# module_rev1.net
KiCad netlist of a schematic drawn in Altium Designer
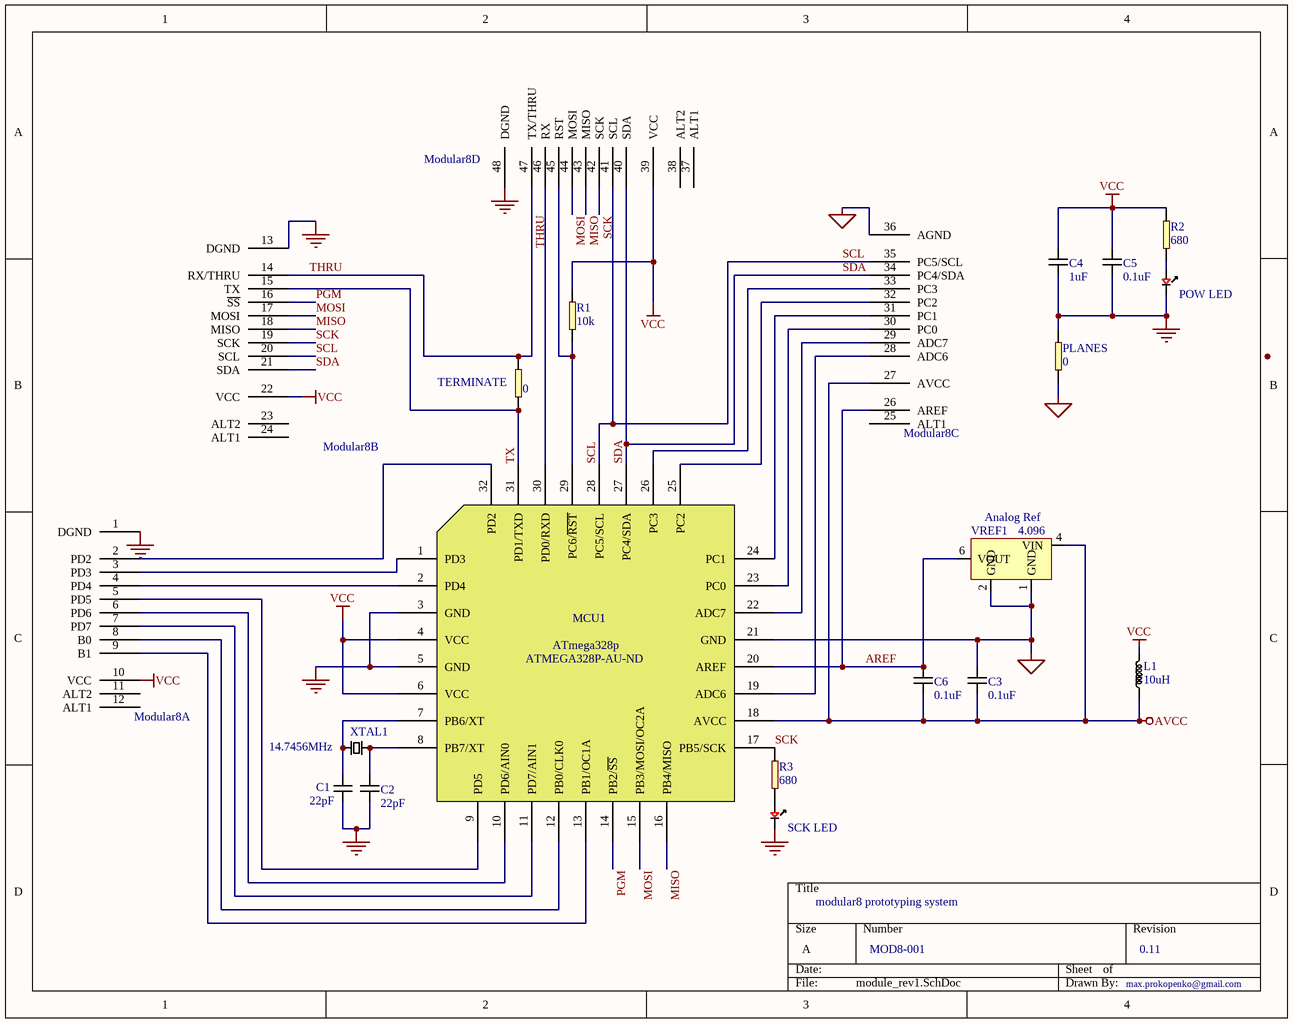
[diagram p0: module_rev1.SchDoc]

(export (version "E")
  (design (tool "Eeschema 10.0.6"))
  (components
    (comp (ref "C1")
      (value "C 22pF 50V")
      (footprint "0603")
      (fields (field (name "C") "22pF"))
      (libsource (lib "") (part "C 22pF 50V_1"))
    )
    (comp (ref "C2")
      (value "C 22pF 50V")
      (footprint "0603")
      (fields (field (name "C") "22pF"))
      (libsource (lib "RLC") (part "C 22pF 50V"))
    )
    (comp (ref "C3")
      (value "C 0.1uF 25V")
      (footprint "0603")
      (fields (field (name "C") "0.1uF"))
      (libsource (lib "RLC") (part "C 0.1uF 25V"))
    )
    (comp (ref "C4")
      (value "C 1uF 25V")
      (footprint "0603")
      (fields (field (name "C") "1uF"))
      (libsource (lib "RLC") (part "C 1uF 25V"))
    )
    (comp (ref "C5")
      (value "C 0.1uF 25V")
      (footprint "0603")
      (fields (field (name "C") "0.1uF"))
      (libsource (lib "RLC") (part "C 0.1uF 25V"))
    )
    (comp (ref "C6")
      (value "C 0.1uF 25V")
      (footprint "0603")
      (fields (field (name "C") "0.1uF"))
      (libsource (lib "RLC") (part "C 0.1uF 25V"))
    )
    (comp (ref "L1")
      (value "L 10uH")
      (footprint "0603")
      (fields (field (name "L") "10uH"))
      (libsource (lib "RLC") (part "L 10uH"))
    )
    (comp (ref "MCU1")
      (value "ATmega328p")
      (footprint "ATmega328p TQFP")
      (fields (field (name "SUPPLIER PART NUMBER 1") "ATMEGA328P-AU-ND"))
      (libsource (lib "OpBots") (part "ATmega328p"))
    )
    (comp (ref "Modular8")
      (value "Modular8")
      (footprint "modular8")
      (libsource (lib "OpBots") (part "Modular8"))
    )
    (comp (ref "PLANES")
      (value "R 0")
      (footprint "0603")
      (fields (field (name "R") "0"))
      (libsource (lib "") (part "R 0_1"))
    )
    (comp (ref "POW LED") (value "LEDR") (footprint "0603") (libsource (lib "OpBots") (part "LEDR")))
    (comp (ref "R1")
      (value "R 10k")
      (footprint "0603")
      (fields (field (name "R") "10k"))
      (libsource (lib "RLC") (part "R 10k"))
    )
    (comp (ref "R2")
      (value "R 680")
      (footprint "0603")
      (fields (field (name "R") "680"))
      (libsource (lib "RLC") (part "R 680"))
    )
    (comp (ref "R3")
      (value "R 680")
      (footprint "0603")
      (fields (field (name "R") "680"))
      (libsource (lib "RLC") (part "R 680"))
    )
    (comp (ref "SCK LED") (value "LEDR") (footprint "0603") (libsource (lib "OpBots") (part "LEDR")))
    (comp (ref "TERMINATE")
      (value "R 0")
      (footprint "0603")
      (fields (field (name "R") "0"))
      (libsource (lib "RLC") (part "R 0"))
    )
    (comp (ref "VREF1")
      (value "Analog Ref")
      (footprint "TSOT-23-6")
      (fields (field (name "VREF") "4.096"))
      (libsource (lib "OpBots") (part "LT1790BCS6"))
    )
    (comp (ref "XTAL1")
      (value "XTAL 14.7456MHz")
      (footprint "XTAL CSM-3X")
      (fields (field (name "FREQUENCY") "14.7456MHz"))
      (libsource (lib "OpBots") (part "XTAL 14.7456MHz"))
    )
  )
  (nets
    (net (code "1") (name "/AREF") (class "Default")
      (node (ref "C6") (pin "1") (pintype "passive"))
      (node (ref "MCU1") (pin "20") (pinfunction "AREF_20") (pintype "passive"))
      (node (ref "Modular8") (pin "26") (pinfunction "AREF_26") (pintype "passive"))
      (node (ref "VREF1") (pin "6") (pinfunction "VOUT_6") (pintype "passive"))
    )
    (net (code "2") (name "/MISO") (class "Default")
      (node (ref "MCU1") (pin "16") (pinfunction "PB4/MISO_16") (pintype "passive"))
      (node (ref "Modular8") (pin "18") (pinfunction "MISO_18") (pintype "passive"))
      (node (ref "Modular8") (pin "43") (pinfunction "MISO_43") (pintype "passive"))
    )
    (net (code "3") (name "/MOSI") (class "Default")
      (node (ref "MCU1") (pin "15") (pinfunction "PB3/MOSI/OC2A_15") (pintype "passive"))
      (node (ref "Modular8") (pin "17") (pinfunction "MOSI_17") (pintype "passive"))
      (node (ref "Modular8") (pin "44") (pinfunction "MOSI_44") (pintype "passive"))
    )
    (net (code "4") (name "/PGM") (class "Default")
      (node (ref "MCU1") (pin "14") (pinfunction "PB2/~{SS}_14") (pintype "passive"))
      (node (ref "Modular8") (pin "16") (pinfunction "~{SS}_16") (pintype "passive"))
    )
    (net (code "5") (name "/SCK") (class "Default")
      (node (ref "MCU1") (pin "17") (pinfunction "PB5/SCK_17") (pintype "passive"))
      (node (ref "Modular8") (pin "19") (pinfunction "SCK_19") (pintype "passive"))
      (node (ref "Modular8") (pin "42") (pinfunction "SCK_42") (pintype "passive"))
      (node (ref "R3") (pin "1") (pintype "passive"))
    )
    (net (code "6") (name "/SCL") (class "Default")
      (node (ref "MCU1") (pin "28") (pinfunction "PC5/SCL_28") (pintype "passive"))
      (node (ref "Modular8") (pin "20") (pinfunction "SCL_20") (pintype "passive"))
      (node (ref "Modular8") (pin "35") (pinfunction "PC5/SCL_35") (pintype "passive"))
      (node (ref "Modular8") (pin "41") (pinfunction "SCL_41") (pintype "passive"))
    )
    (net (code "7") (name "/SDA") (class "Default")
      (node (ref "MCU1") (pin "27") (pinfunction "PC4/SDA_27") (pintype "passive"))
      (node (ref "Modular8") (pin "21") (pinfunction "SDA_21") (pintype "passive"))
      (node (ref "Modular8") (pin "34") (pinfunction "PC4/SDA_34") (pintype "passive"))
      (node (ref "Modular8") (pin "40") (pinfunction "SDA_40") (pintype "passive"))
    )
    (net (code "8") (name "/THRU") (class "Default")
      (node (ref "Modular8") (pin "14") (pinfunction "RX/THRU_14") (pintype "passive"))
      (node (ref "Modular8") (pin "47") (pinfunction "TX/THRU_47") (pintype "passive"))
      (node (ref "TERMINATE") (pin "1") (pintype "passive"))
    )
    (net (code "9") (name "/TX") (class "Default")
      (node (ref "MCU1") (pin "31") (pinfunction "PD1/TXD_31") (pintype "passive"))
      (node (ref "Modular8") (pin "15") (pinfunction "TX_15") (pintype "passive"))
      (node (ref "TERMINATE") (pin "2") (pintype "passive"))
    )
    (net (code "10") (name "AGND") (class "Default")
      (node (ref "C3") (pin "1") (pintype "passive"))
      (node (ref "MCU1") (pin "21") (pinfunction "GND_21") (pintype "passive"))
      (node (ref "Modular8") (pin "36") (pinfunction "AGND_36") (pintype "passive"))
      (node (ref "PLANES") (pin "1") (pintype "passive"))
      (node (ref "VREF1") (pin "1") (pinfunction "GND_1") (pintype "passive"))
      (node (ref "VREF1") (pin "2") (pinfunction "GND_2") (pintype "passive"))
    )
    (net (code "11") (name "AVCC") (class "Default")
      (node (ref "C3") (pin "2") (pintype "passive"))
      (node (ref "C6") (pin "2") (pintype "passive"))
      (node (ref "L1") (pin "2") (pintype "passive"))
      (node (ref "MCU1") (pin "18") (pinfunction "AVCC_18") (pintype "passive"))
      (node (ref "Modular8") (pin "27") (pinfunction "AVCC_27") (pintype "passive"))
      (node (ref "VREF1") (pin "4") (pinfunction "VIN_4") (pintype "passive"))
    )
    (net (code "12") (name "DGND") (class "Default")
      (node (ref "C1") (pin "1") (pintype "passive"))
      (node (ref "C2") (pin "2") (pintype "passive"))
      (node (ref "C4") (pin "2") (pintype "passive"))
      (node (ref "C5") (pin "2") (pintype "passive"))
      (node (ref "MCU1") (pin "3") (pinfunction "GND_3") (pintype "passive"))
      (node (ref "MCU1") (pin "5") (pinfunction "GND_5") (pintype "passive"))
      (node (ref "Modular8") (pin "1") (pinfunction "DGND_1") (pintype "passive"))
      (node (ref "Modular8") (pin "13") (pinfunction "DGND_13") (pintype "passive"))
      (node (ref "Modular8") (pin "48") (pinfunction "DGND_48") (pintype "passive"))
      (node (ref "PLANES") (pin "2") (pintype "passive"))
      (node (ref "POW LED") (pin "1") (pinfunction "K_1") (pintype "passive"))
      (node (ref "SCK LED") (pin "1") (pinfunction "K_1") (pintype "passive"))
    )
    (net (code "13") (name "Net-(MCU1-ADC6)") (class "Default")
      (node (ref "MCU1") (pin "19") (pinfunction "ADC6_19") (pintype "passive"))
      (node (ref "Modular8") (pin "28") (pinfunction "ADC6_28") (pintype "passive"))
    )
    (net (code "14") (name "Net-(MCU1-ADC7)") (class "Default")
      (node (ref "MCU1") (pin "22") (pinfunction "ADC7_22") (pintype "passive"))
      (node (ref "Modular8") (pin "29") (pinfunction "ADC7_29") (pintype "passive"))
    )
    (net (code "15") (name "Net-(MCU1-PB0{slash}CLK0)") (class "Default")
      (node (ref "MCU1") (pin "12") (pinfunction "PB0/CLK0_12") (pintype "passive"))
      (node (ref "Modular8") (pin "8") (pinfunction "B0_8") (pintype "passive"))
    )
    (net (code "16") (name "Net-(MCU1-PB1{slash}OC1A)") (class "Default")
      (node (ref "MCU1") (pin "13") (pinfunction "PB1/OC1A_13") (pintype "passive"))
      (node (ref "Modular8") (pin "9") (pinfunction "B1_9") (pintype "passive"))
    )
    (net (code "17") (name "Net-(MCU1-PB6{slash}XT)") (class "Default")
      (node (ref "C1") (pin "2") (pintype "passive"))
      (node (ref "MCU1") (pin "7") (pinfunction "PB6/XT_7") (pintype "passive"))
      (node (ref "XTAL1") (pin "1") (pintype "passive"))
    )
    (net (code "18") (name "Net-(MCU1-PB7{slash}XT)") (class "Default")
      (node (ref "C2") (pin "1") (pintype "passive"))
      (node (ref "MCU1") (pin "8") (pinfunction "PB7/XT_8") (pintype "passive"))
      (node (ref "XTAL1") (pin "2") (pintype "passive"))
    )
    (net (code "19") (name "Net-(MCU1-PC0)") (class "Default")
      (node (ref "MCU1") (pin "23") (pinfunction "PC0_23") (pintype "passive"))
      (node (ref "Modular8") (pin "30") (pinfunction "PC0_30") (pintype "passive"))
    )
    (net (code "20") (name "Net-(MCU1-PC1)") (class "Default")
      (node (ref "MCU1") (pin "24") (pinfunction "PC1_24") (pintype "passive"))
      (node (ref "Modular8") (pin "31") (pinfunction "PC1_31") (pintype "passive"))
    )
    (net (code "21") (name "Net-(MCU1-PC2)") (class "Default")
      (node (ref "MCU1") (pin "25") (pinfunction "PC2_25") (pintype "passive"))
      (node (ref "Modular8") (pin "32") (pinfunction "PC2_32") (pintype "passive"))
    )
    (net (code "22") (name "Net-(MCU1-PC3)") (class "Default")
      (node (ref "MCU1") (pin "26") (pinfunction "PC3_26") (pintype "passive"))
      (node (ref "Modular8") (pin "33") (pinfunction "PC3_33") (pintype "passive"))
    )
    (net (code "23") (name "Net-(MCU1-PC6{slash}~{RST})") (class "Default")
      (node (ref "MCU1") (pin "29") (pinfunction "PC6/~{RST}_29") (pintype "passive"))
      (node (ref "Modular8") (pin "45") (pinfunction "RST_45") (pintype "passive"))
      (node (ref "R1") (pin "2") (pintype "passive"))
    )
    (net (code "24") (name "Net-(MCU1-PD0{slash}RXD)") (class "Default")
      (node (ref "MCU1") (pin "30") (pinfunction "PD0/RXD_30") (pintype "passive"))
      (node (ref "Modular8") (pin "46") (pinfunction "RX_46") (pintype "passive"))
    )
    (net (code "25") (name "Net-(MCU1-PD2)") (class "Default")
      (node (ref "MCU1") (pin "32") (pinfunction "PD2_32") (pintype "passive"))
      (node (ref "Modular8") (pin "2") (pinfunction "PD2_2") (pintype "passive"))
    )
    (net (code "26") (name "Net-(MCU1-PD3)") (class "Default")
      (node (ref "MCU1") (pin "1") (pinfunction "PD3_1") (pintype "passive"))
      (node (ref "Modular8") (pin "3") (pinfunction "PD3_3") (pintype "passive"))
    )
    (net (code "27") (name "Net-(MCU1-PD4)") (class "Default")
      (node (ref "MCU1") (pin "2") (pinfunction "PD4_2") (pintype "passive"))
      (node (ref "Modular8") (pin "4") (pinfunction "PD4_4") (pintype "passive"))
    )
    (net (code "28") (name "Net-(MCU1-PD5)") (class "Default")
      (node (ref "MCU1") (pin "9") (pinfunction "PD5_9") (pintype "passive"))
      (node (ref "Modular8") (pin "5") (pinfunction "PD5_5") (pintype "passive"))
    )
    (net (code "29") (name "Net-(MCU1-PD6{slash}AIN0)") (class "Default")
      (node (ref "MCU1") (pin "10") (pinfunction "PD6/AIN0_10") (pintype "passive"))
      (node (ref "Modular8") (pin "6") (pinfunction "PD6_6") (pintype "passive"))
    )
    (net (code "30") (name "Net-(MCU1-PD7{slash}AIN1)") (class "Default")
      (node (ref "MCU1") (pin "11") (pinfunction "PD7/AIN1_11") (pintype "passive"))
      (node (ref "Modular8") (pin "7") (pinfunction "PD7_7") (pintype "passive"))
    )
    (net (code "31") (name "Net-(POW LED-A)") (class "Default")
      (node (ref "POW LED") (pin "2") (pinfunction "A_2") (pintype "passive"))
      (node (ref "R2") (pin "2") (pintype "passive"))
    )
    (net (code "32") (name "Net-(SCK LED-A)") (class "Default")
      (node (ref "R3") (pin "2") (pintype "passive"))
      (node (ref "SCK LED") (pin "2") (pinfunction "A_2") (pintype "passive"))
    )
    (net (code "33") (name "VCC") (class "Default")
      (node (ref "C4") (pin "1") (pintype "passive"))
      (node (ref "C5") (pin "1") (pintype "passive"))
      (node (ref "L1") (pin "1") (pintype "passive"))
      (node (ref "MCU1") (pin "4") (pinfunction "VCC_4") (pintype "passive"))
      (node (ref "MCU1") (pin "6") (pinfunction "VCC_6") (pintype "passive"))
      (node (ref "Modular8") (pin "10") (pinfunction "VCC_10") (pintype "passive"))
      (node (ref "Modular8") (pin "22") (pinfunction "VCC_22") (pintype "passive"))
      (node (ref "Modular8") (pin "39") (pinfunction "VCC_39") (pintype "passive"))
      (node (ref "R1") (pin "1") (pintype "passive"))
      (node (ref "R2") (pin "1") (pintype "passive"))
    )
    (net (code "34") (name "unconnected-(Modular8A-ALT1-Pad12)") (class "Default")
      (node (ref "Modular8") (pin "12") (pinfunction "ALT1_12") (pintype "passive"))
    )
    (net (code "35") (name "unconnected-(Modular8A-ALT2-Pad11)") (class "Default")
      (node (ref "Modular8") (pin "11") (pinfunction "ALT2_11") (pintype "passive"))
    )
    (net (code "36") (name "unconnected-(Modular8B-ALT1-Pad24)") (class "Default")
      (node (ref "Modular8") (pin "24") (pinfunction "ALT1_24") (pintype "passive"))
    )
    (net (code "37") (name "unconnected-(Modular8B-ALT2-Pad23)") (class "Default")
      (node (ref "Modular8") (pin "23") (pinfunction "ALT2_23") (pintype "passive"))
    )
    (net (code "38") (name "unconnected-(Modular8C-ALT1-Pad25)") (class "Default")
      (node (ref "Modular8") (pin "25") (pinfunction "ALT1_25") (pintype "passive"))
    )
    (net (code "39") (name "unconnected-(Modular8D-ALT1-Pad37)") (class "Default")
      (node (ref "Modular8") (pin "37") (pinfunction "ALT1_37") (pintype "passive"))
    )
    (net (code "40") (name "unconnected-(Modular8D-ALT2-Pad38)") (class "Default")
      (node (ref "Modular8") (pin "38") (pinfunction "ALT2_38") (pintype "passive"))
    )
  )
)
